# CON_ATA_18.net
KiCad netlist of a schematic drawn in Altium Designer
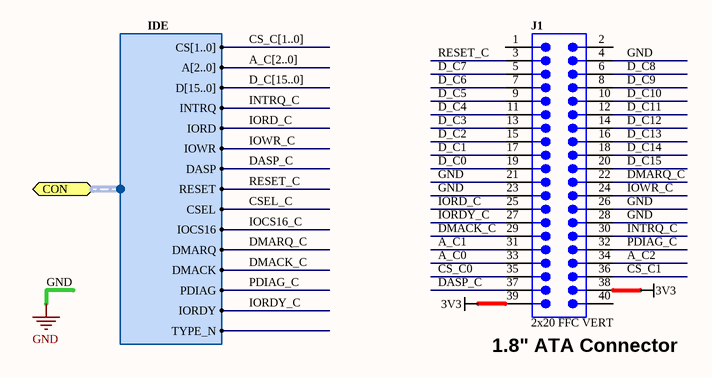
[diagram p0: CON_ATA_18.SchDoc]

(export (version "E")
  (design (tool "Eeschema 10.0.6"))
  (components
    (comp (ref "J1")
      (value "2x20 FFC VERT")
      (footprint "FFC40-05-VERT")
      (description "Header FFC, 2x20 pin Vertical, 0.5mm")
      (libsource (lib "AltiumDesignLibrary") (part "CON-FFC-2x20-VERT"))
    )
  )
  (nets
    (net (code "2") (name "/A_C0") (class "Default")
      (node (ref "J1") (pin "33") (pinfunction "33_33") (pintype "passive"))
    )
    (net (code "3") (name "/A_C1") (class "Default")
      (node (ref "J1") (pin "31") (pinfunction "31_31") (pintype "passive"))
    )
    (net (code "4") (name "/A_C2") (class "Default")
      (node (ref "J1") (pin "34") (pinfunction "34_34") (pintype "passive"))
    )
    (net (code "7") (name "/CS_C0") (class "Default")
      (node (ref "J1") (pin "35") (pinfunction "35_35") (pintype "passive"))
    )
    (net (code "8") (name "/CS_C1") (class "Default")
      (node (ref "J1") (pin "36") (pinfunction "36_36") (pintype "passive"))
    )
    (net (code "10") (name "/DASP_C") (class "Default")
      (node (ref "J1") (pin "37") (pinfunction "37_37") (pintype "passive"))
    )
    (net (code "11") (name "/DMACK_C") (class "Default")
      (node (ref "J1") (pin "29") (pinfunction "29_29") (pintype "passive"))
    )
    (net (code "12") (name "/DMARQ_C") (class "Default")
      (node (ref "J1") (pin "22") (pinfunction "22_22") (pintype "passive"))
    )
    (net (code "13") (name "/D_C0") (class "Default")
      (node (ref "J1") (pin "19") (pinfunction "19_19") (pintype "passive"))
    )
    (net (code "14") (name "/D_C1") (class "Default")
      (node (ref "J1") (pin "17") (pinfunction "17_17") (pintype "passive"))
    )
    (net (code "15") (name "/D_C2") (class "Default")
      (node (ref "J1") (pin "15") (pinfunction "15_15") (pintype "passive"))
    )
    (net (code "16") (name "/D_C3") (class "Default")
      (node (ref "J1") (pin "13") (pinfunction "13_13") (pintype "passive"))
    )
    (net (code "17") (name "/D_C4") (class "Default")
      (node (ref "J1") (pin "11") (pinfunction "11_11") (pintype "passive"))
    )
    (net (code "18") (name "/D_C5") (class "Default")
      (node (ref "J1") (pin "9") (pinfunction "9_9") (pintype "passive"))
    )
    (net (code "19") (name "/D_C6") (class "Default")
      (node (ref "J1") (pin "7") (pinfunction "7_7") (pintype "passive"))
    )
    (net (code "20") (name "/D_C7") (class "Default")
      (node (ref "J1") (pin "5") (pinfunction "5_5") (pintype "passive"))
    )
    (net (code "21") (name "/D_C8") (class "Default")
      (node (ref "J1") (pin "6") (pinfunction "6_6") (pintype "passive"))
    )
    (net (code "22") (name "/D_C9") (class "Default")
      (node (ref "J1") (pin "8") (pinfunction "8_8") (pintype "passive"))
    )
    (net (code "23") (name "/D_C10") (class "Default")
      (node (ref "J1") (pin "10") (pinfunction "10_10") (pintype "passive"))
    )
    (net (code "24") (name "/D_C11") (class "Default")
      (node (ref "J1") (pin "12") (pinfunction "12_12") (pintype "passive"))
    )
    (net (code "25") (name "/D_C12") (class "Default")
      (node (ref "J1") (pin "14") (pinfunction "14_14") (pintype "passive"))
    )
    (net (code "26") (name "/D_C13") (class "Default")
      (node (ref "J1") (pin "16") (pinfunction "16_16") (pintype "passive"))
    )
    (net (code "27") (name "/D_C14") (class "Default")
      (node (ref "J1") (pin "18") (pinfunction "18_18") (pintype "passive"))
    )
    (net (code "28") (name "/D_C15") (class "Default")
      (node (ref "J1") (pin "20") (pinfunction "20_20") (pintype "passive"))
    )
    (net (code "30") (name "/INTRQ_C") (class "Default")
      (node (ref "J1") (pin "30") (pinfunction "30_30") (pintype "passive"))
    )
    (net (code "32") (name "/IORDY_C") (class "Default")
      (node (ref "J1") (pin "27") (pinfunction "27_27") (pintype "passive"))
    )
    (net (code "33") (name "/IORD_C") (class "Default")
      (node (ref "J1") (pin "25") (pinfunction "25_25") (pintype "passive"))
    )
    (net (code "34") (name "/IOWR_C") (class "Default")
      (node (ref "J1") (pin "24") (pinfunction "24_24") (pintype "passive"))
    )
    (net (code "35") (name "/PDIAG_C") (class "Default")
      (node (ref "J1") (pin "32") (pinfunction "32_32") (pintype "passive"))
    )
    (net (code "36") (name "/RESET_C") (class "Default")
      (node (ref "J1") (pin "3") (pinfunction "3_3") (pintype "passive"))
    )
    (net (code "38") (name "3V3") (class "Default")
      (node (ref "J1") (pin "38") (pinfunction "38_38") (pintype "passive"))
      (node (ref "J1") (pin "39") (pinfunction "39_39") (pintype "passive"))
    )
    (net (code "39") (name "GND") (class "Default")
      (node (ref "J1") (pin "21") (pinfunction "21_21") (pintype "passive"))
      (node (ref "J1") (pin "23") (pinfunction "23_23") (pintype "passive"))
      (node (ref "J1") (pin "26") (pinfunction "26_26") (pintype "passive"))
      (node (ref "J1") (pin "28") (pinfunction "28_28") (pintype "passive"))
      (node (ref "J1") (pin "4") (pinfunction "4_4") (pintype "passive"))
    )
    (net (code "40") (name "unconnected-(J1-Pad1)") (class "Default")
      (node (ref "J1") (pin "1") (pinfunction "1_1") (pintype "passive"))
    )
    (net (code "41") (name "unconnected-(J1-Pad2)") (class "Default")
      (node (ref "J1") (pin "2") (pinfunction "2_2") (pintype "passive"))
    )
    (net (code "42") (name "unconnected-(J1-Pad40)") (class "Default")
      (node (ref "J1") (pin "40") (pinfunction "40_40") (pintype "passive"))
    )
  )
)
